# Arduino_DDS_Shield_Rev_6.net
KiCad netlist of a schematic drawn in Altium Designer
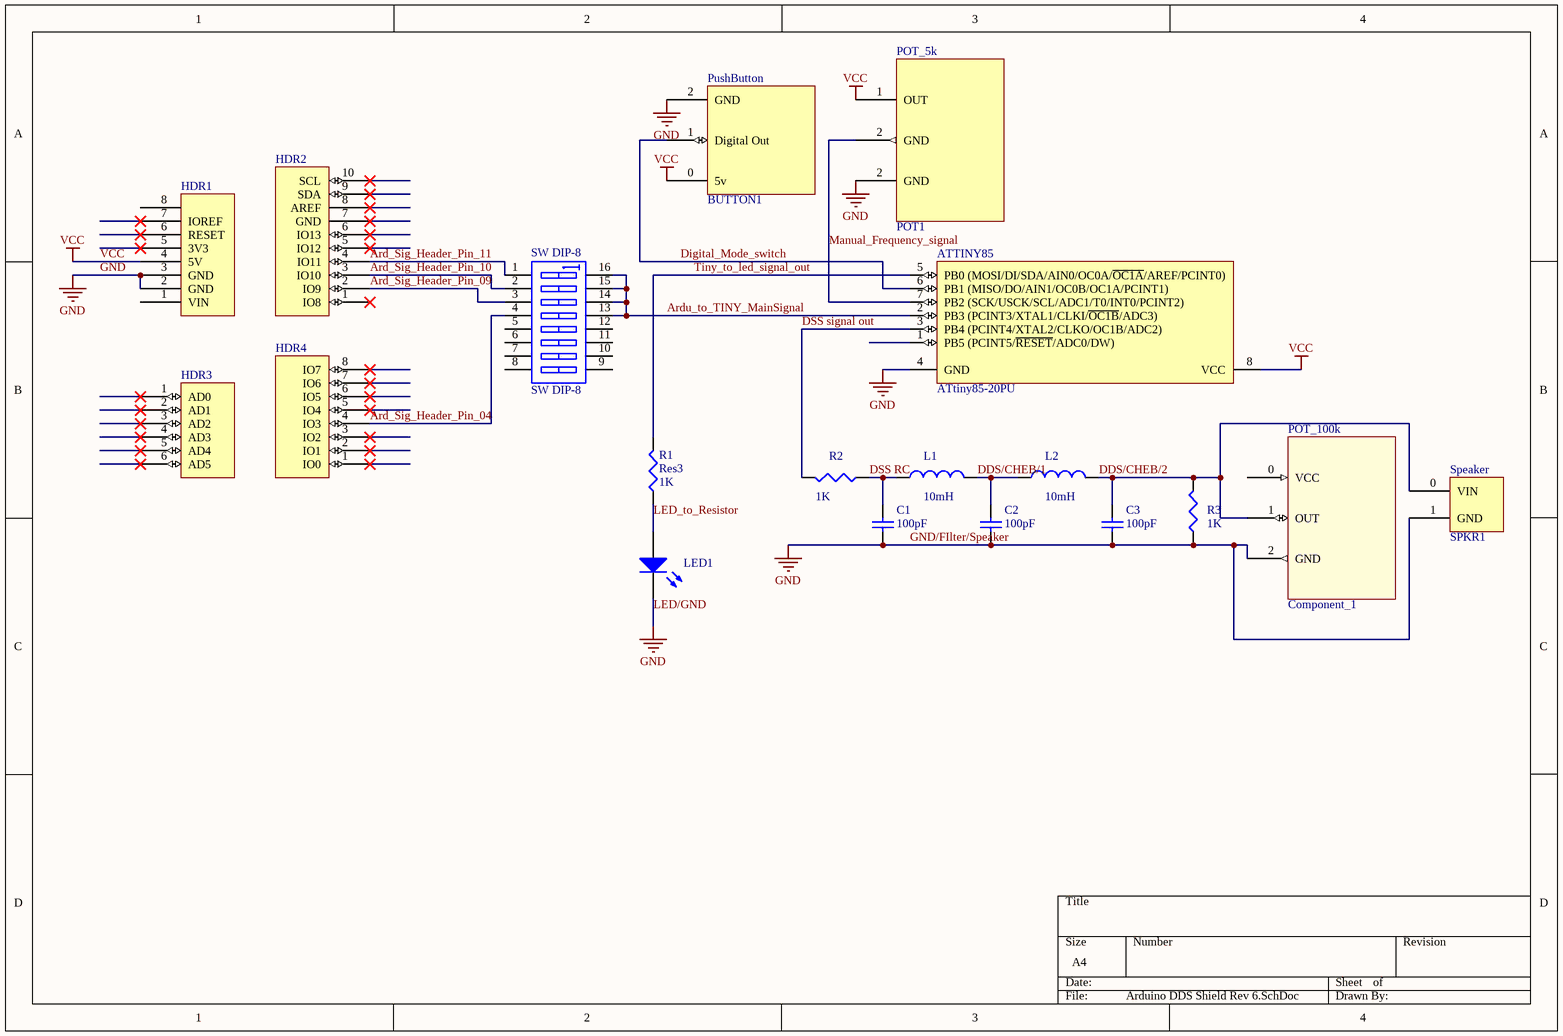
[diagram p0: Arduino DDS Shield Rev 6.SchDoc]

(export (version "E")
  (design (tool "Eeschema 10.0.6"))
  (components
    (comp (ref "ATTINY85")
      (value "ATtiny85-20PU")
      (footprint "8P3")
      (fields (field (name "PUBLISHER") "Altium Limited"))
      (libsource (lib "Atmel Microcontroller 8-Bit tinyAVR") (part "ATtiny85-20PU"))
    )
    (comp (ref "C1")
      (value "100pF")
      (footprint "1608[0603]")
      (description "Capacitor (Semiconductor SIM Model)")
      (fields (field (name "Comment") "Cap Semi") (field (name "PUBLISHER") "Altium Limited"))
      (libsource (lib "Miscellaneous Devices") (part "Cap Semi"))
    )
    (comp (ref "C2")
      (value "100pF")
      (footprint "1608[0603]")
      (description "Capacitor (Semiconductor SIM Model)")
      (fields (field (name "Comment") "Cap Semi") (field (name "PUBLISHER") "Altium Limited"))
      (libsource (lib "Miscellaneous Devices") (part "Cap Semi"))
    )
    (comp (ref "C3")
      (value "100pF")
      (footprint "1608[0603]")
      (description "Capacitor (Semiconductor SIM Model)")
      (fields (field (name "Comment") "Cap Semi") (field (name "PUBLISHER") "Altium Limited"))
      (libsource (lib "Miscellaneous Devices") (part "Cap Semi"))
    )
    (comp (ref "HDR1")
      (value "POWER_UNO")
      (footprint "Header 8x1 8.5mm")
      (libsource (lib "Header") (part "POWER_UNO"))
    )
    (comp (ref "HDR2")
      (value "IOH")
      (footprint "Header:Header 10x1 8.5mm")
      (libsource (lib "Header") (part "IOH"))
    )
    (comp (ref "HDR3")
      (value "AD")
      (footprint "Header:Header 6x1 8.5mm")
      (libsource (lib "Header") (part "AD"))
    )
    (comp (ref "HDR4") (value "IOL") (footprint "Header 8x1 8.5mm") (libsource (lib "Header") (part "IOL")))
    (comp (ref "L1")
      (value "10mH")
      (footprint "AXIAL-0.5")
      (description "Inductor")
      (fields (field (name "PUBLISHER") "Altium Limited"))
      (libsource (lib "Miscellaneous Devices") (part "Inductor"))
    )
    (comp (ref "L2")
      (value "10mH")
      (footprint "AXIAL-0.5")
      (description "Inductor")
      (fields (field (name "PUBLISHER") "Altium Limited"))
      (libsource (lib "Miscellaneous Devices") (part "Inductor"))
    )
    (comp (ref "LED1")
      (value "LED1")
      (footprint "LED-1")
      (description "Typical RED GaAs LED")
      (fields (field (name "PUBLISHER") "Altium Limited"))
      (libsource (lib "Miscellaneous Devices") (part "LED1"))
    )
    (comp (ref "POT_5k")
      (value "POT1")
      (footprint "Pot5k")
      (description "5k RES")
      (libsource (lib "PotLib_Rev_5") (part "Component_1"))
    )
    (comp (ref "POT_100k")
      (value "Component_1")
      (footprint "pot100k")
      (description "5k RES")
      (libsource (lib "PotLib_v_2") (part "Component_1"))
    )
    (comp (ref "PushButton")
      (value "BUTTON1")
      (footprint "PushButtonFrame")
      (libsource (lib "Pushbutton_V_5") (part "PushButton"))
    )
    (comp (ref "R1")
      (value "Res3")
      (footprint "J1-0603")
      (description "Resistor")
      (fields (field (name "ALTIUM_VALUE") "1K") (field (name "PUBLISHER") "Altium Limited"))
      (libsource (lib "Miscellaneous Devices") (part "Res3"))
    )
    (comp (ref "R2")
      (value "1K")
      (footprint "J1-0603")
      (description "Resistor")
      (fields (field (name "Comment") "Res3") (field (name "PUBLISHER") "Altium Limited"))
      (libsource (lib "Miscellaneous Devices") (part "Res3"))
    )
    (comp (ref "R3")
      (value "1K")
      (footprint "J1-0603")
      (description "Resistor")
      (fields (field (name "Comment") "Res3") (field (name "PUBLISHER") "Altium Limited"))
      (libsource (lib "Miscellaneous Devices") (part "Res3"))
    )
    (comp (ref "Speaker")
      (value "SPKR1")
      (footprint "PCBComponent_1")
      (libsource (lib "Schlib1_rev_01") (part "Component_1"))
    )
    (comp (ref "SW DIP-8")
      (value "SW DIP-8")
      (footprint "DIP8posSolder")
      (description "DIP Switch, 8 Position, SPST")
      (fields (field (name "PUBLISHER") "Altium Limited"))
      (libsource (lib "Miscellaneous Devices") (part "SW DIP-8"))
    )
  )
  (nets
    (net (code "2") (name "/Ard_Sig_Header_Pin_04") (class "Default")
      (node (ref "HDR4") (pin "4") (pinfunction "IO3_4") (pintype "bidirectional"))
      (node (ref "SW DIP-8") (pin "4") (pinfunction "A4_4") (pintype "passive"))
    )
    (net (code "3") (name "/Ard_Sig_Header_Pin_09") (class "Default")
      (node (ref "HDR2") (pin "2") (pinfunction "IO9_2") (pintype "bidirectional"))
      (node (ref "SW DIP-8") (pin "3") (pinfunction "A3_3") (pintype "passive"))
    )
    (net (code "4") (name "/Ard_Sig_Header_Pin_10") (class "Default")
      (node (ref "HDR2") (pin "3") (pinfunction "IO10_3") (pintype "bidirectional"))
      (node (ref "SW DIP-8") (pin "2") (pinfunction "A2_2") (pintype "passive"))
    )
    (net (code "5") (name "/Ard_Sig_Header_Pin_11") (class "Default")
      (node (ref "HDR2") (pin "4") (pinfunction "IO11_4") (pintype "bidirectional"))
      (node (ref "SW DIP-8") (pin "1") (pinfunction "A1_1") (pintype "passive"))
    )
    (net (code "6") (name "/Ardu_to_TINY_MainSignal") (class "Default")
      (node (ref "ATTINY85") (pin "2") (pinfunction "PB3_(PCINT3/XTAL1/CLKI/~{OC1B}/ADC3)_2") (pintype "bidirectional"))
      (node (ref "SW DIP-8") (pin "13") (pinfunction "B4_13") (pintype "passive"))
      (node (ref "SW DIP-8") (pin "14") (pinfunction "B3_14") (pintype "passive"))
      (node (ref "SW DIP-8") (pin "15") (pinfunction "B2_15") (pintype "passive"))
      (node (ref "SW DIP-8") (pin "16") (pinfunction "B1_16") (pintype "passive"))
    )
    (net (code "7") (name "/DDS{slash}CHEB{slash}1") (class "Default")
      (node (ref "C2") (pin "2") (pinfunction "2_2") (pintype "passive"))
      (node (ref "L1") (pin "2") (pinfunction "2_2") (pintype "passive"))
      (node (ref "L2") (pin "1") (pinfunction "1_1") (pintype "passive"))
    )
    (net (code "8") (name "/DDS{slash}CHEB{slash}2") (class "Default")
      (node (ref "C3") (pin "2") (pinfunction "2_2") (pintype "passive"))
      (node (ref "L2") (pin "2") (pinfunction "2_2") (pintype "passive"))
      (node (ref "POT_100k") (pin "1") (pinfunction "OUT_1") (pintype "bidirectional"))
      (node (ref "R3") (pin "2") (pinfunction "2_2") (pintype "passive"))
      (node (ref "Speaker") (pin "0") (pinfunction "VIN_0") (pintype "power_in"))
    )
    (net (code "9") (name "/DSS RC") (class "Default")
      (node (ref "C1") (pin "2") (pinfunction "2_2") (pintype "passive"))
      (node (ref "L1") (pin "1") (pinfunction "1_1") (pintype "passive"))
      (node (ref "R2") (pin "1") (pinfunction "1_1") (pintype "passive"))
    )
    (net (code "10") (name "/DSS signal out") (class "Default")
      (node (ref "ATTINY85") (pin "3") (pinfunction "PB4_(PCINT4/XTAL2/CLKO/OC1B/ADC2)_3") (pintype "bidirectional"))
      (node (ref "R2") (pin "2") (pinfunction "2_2") (pintype "passive"))
    )
    (net (code "11") (name "/Digital_Mode_switch") (class "Default")
      (node (ref "ATTINY85") (pin "6") (pinfunction "PB1_(MISO/DO/AIN1/OC0B/OC1A/PCINT1)_6") (pintype "bidirectional"))
      (node (ref "PushButton") (pin "1") (pinfunction "Digital_Out_1") (pintype "bidirectional"))
    )
    (net (code "12") (name "/LED_to_Resistor") (class "Default")
      (node (ref "LED1") (pin "1") (pinfunction "A_1") (pintype "passive"))
      (node (ref "R1") (pin "1") (pinfunction "1_1") (pintype "passive"))
    )
    (net (code "13") (name "/Manual_Frequency_signal") (class "Default")
      (node (ref "ATTINY85") (pin "7") (pinfunction "PB2_(SCK/USCK/SCL/ADC1/T0/INT0/PCINT2)_7") (pintype "bidirectional"))
      (node (ref "POT_5k") (pin "2") (pinfunction "GND_2") (pintype "output"))
    )
    (net (code "14") (name "/Tiny_to_led_signal_out") (class "Default")
      (node (ref "ATTINY85") (pin "5") (pinfunction "PB0_(MOSI/DI/SDA/AIN0/OC0A/~{OC1A}/AREF/PCINT0)_5") (pintype "bidirectional"))
      (node (ref "R1") (pin "2") (pinfunction "2_2") (pintype "passive"))
    )
    (net (code "15") (name "GND") (class "Default")
      (node (ref "ATTINY85") (pin "4") (pinfunction "GND_4") (pintype "power_in"))
      (node (ref "C1") (pin "1") (pinfunction "1_1") (pintype "passive"))
      (node (ref "C2") (pin "1") (pinfunction "1_1") (pintype "passive"))
      (node (ref "C3") (pin "1") (pinfunction "1_1") (pintype "passive"))
      (node (ref "HDR1") (pin "2") (pinfunction "GND_2") (pintype "power_in"))
      (node (ref "HDR1") (pin "3") (pinfunction "GND_3") (pintype "power_in"))
      (node (ref "LED1") (pin "2") (pinfunction "K_2") (pintype "passive"))
      (node (ref "POT_100k") (pin "2") (pinfunction "GND_2") (pintype "output"))
      (node (ref "POT_5k") (pin "2") (pinfunction "GND_2") (pintype "power_in"))
      (node (ref "PushButton") (pin "2") (pinfunction "GND_2") (pintype "power_in"))
      (node (ref "R3") (pin "1") (pinfunction "1_1") (pintype "passive"))
      (node (ref "Speaker") (pin "1") (pinfunction "GND_1") (pintype "power_in"))
    )
    (net (code "16") (name "VCC") (class "Default")
      (node (ref "ATTINY85") (pin "8") (pinfunction "VCC_8") (pintype "power_in"))
      (node (ref "HDR1") (pin "4") (pinfunction "5V_4") (pintype "power_in"))
      (node (ref "POT_5k") (pin "1") (pinfunction "OUT_1") (pintype "power_in"))
      (node (ref "PushButton") (pin "0") (pinfunction "5v_0") (pintype "power_in"))
    )
    (net (code "17") (name "unconnected-(ATTINY85-PB5_(PCINT5{slash}~{RESET}{slash}ADC0{slash}DW)-Pad1)") (class "Default")
      (node (ref "ATTINY85") (pin "1") (pinfunction "PB5_(PCINT5/~{RESET}/ADC0/DW)_1") (pintype "bidirectional"))
    )
    (net (code "18") (name "unconnected-(HDR1-3V3-Pad5)") (class "Default")
      (node (ref "HDR1") (pin "5") (pinfunction "3V3_5") (pintype "power_in+no_connect"))
    )
    (net (code "19") (name "unconnected-(HDR1-IOREF-Pad7)") (class "Default")
      (node (ref "HDR1") (pin "7") (pinfunction "IOREF_7") (pintype "power_in+no_connect"))
    )
    (net (code "20") (name "unconnected-(HDR1-Pad8)") (class "Default")
      (node (ref "HDR1") (pin "8") (pintype "passive"))
    )
    (net (code "21") (name "unconnected-(HDR1-RESET-Pad6)") (class "Default")
      (node (ref "HDR1") (pin "6") (pinfunction "RESET_6") (pintype "passive+no_connect"))
    )
    (net (code "22") (name "unconnected-(HDR1-VIN-Pad1)") (class "Default")
      (node (ref "HDR1") (pin "1") (pinfunction "VIN_1") (pintype "power_in"))
    )
    (net (code "23") (name "unconnected-(HDR2-AREF-Pad8)") (class "Default")
      (node (ref "HDR2") (pin "8") (pinfunction "AREF_8") (pintype "passive+no_connect"))
    )
    (net (code "24") (name "unconnected-(HDR2-GND-Pad7)") (class "Default")
      (node (ref "HDR2") (pin "7") (pinfunction "GND_7") (pintype "power_in+no_connect"))
    )
    (net (code "25") (name "unconnected-(HDR2-IO8-Pad1)") (class "Default")
      (node (ref "HDR2") (pin "1") (pinfunction "IO8_1") (pintype "bidirectional+no_connect"))
    )
    (net (code "26") (name "unconnected-(HDR2-IO12-Pad5)") (class "Default")
      (node (ref "HDR2") (pin "5") (pinfunction "IO12_5") (pintype "bidirectional+no_connect"))
    )
    (net (code "27") (name "unconnected-(HDR2-IO13-Pad6)") (class "Default")
      (node (ref "HDR2") (pin "6") (pinfunction "IO13_6") (pintype "bidirectional+no_connect"))
    )
    (net (code "28") (name "unconnected-(HDR2-SCL-Pad10)") (class "Default")
      (node (ref "HDR2") (pin "10") (pinfunction "SCL_10") (pintype "bidirectional+no_connect"))
    )
    (net (code "29") (name "unconnected-(HDR2-SDA-Pad9)") (class "Default")
      (node (ref "HDR2") (pin "9") (pinfunction "SDA_9") (pintype "bidirectional+no_connect"))
    )
    (net (code "30") (name "unconnected-(HDR3-AD0-Pad1)") (class "Default")
      (node (ref "HDR3") (pin "1") (pinfunction "AD0_1") (pintype "bidirectional+no_connect"))
    )
    (net (code "31") (name "unconnected-(HDR3-AD1-Pad2)") (class "Default")
      (node (ref "HDR3") (pin "2") (pinfunction "AD1_2") (pintype "bidirectional+no_connect"))
    )
    (net (code "32") (name "unconnected-(HDR3-AD2-Pad3)") (class "Default")
      (node (ref "HDR3") (pin "3") (pinfunction "AD2_3") (pintype "bidirectional+no_connect"))
    )
    (net (code "33") (name "unconnected-(HDR3-AD3-Pad4)") (class "Default")
      (node (ref "HDR3") (pin "4") (pinfunction "AD3_4") (pintype "bidirectional+no_connect"))
    )
    (net (code "34") (name "unconnected-(HDR3-AD4-Pad5)") (class "Default")
      (node (ref "HDR3") (pin "5") (pinfunction "AD4_5") (pintype "bidirectional+no_connect"))
    )
    (net (code "35") (name "unconnected-(HDR3-AD5-Pad6)") (class "Default")
      (node (ref "HDR3") (pin "6") (pinfunction "AD5_6") (pintype "bidirectional+no_connect"))
    )
    (net (code "36") (name "unconnected-(HDR4-IO0-Pad1)") (class "Default")
      (node (ref "HDR4") (pin "1") (pinfunction "IO0_1") (pintype "bidirectional+no_connect"))
    )
    (net (code "37") (name "unconnected-(HDR4-IO1-Pad2)") (class "Default")
      (node (ref "HDR4") (pin "2") (pinfunction "IO1_2") (pintype "bidirectional+no_connect"))
    )
    (net (code "38") (name "unconnected-(HDR4-IO2-Pad3)") (class "Default")
      (node (ref "HDR4") (pin "3") (pinfunction "IO2_3") (pintype "bidirectional+no_connect"))
    )
    (net (code "39") (name "unconnected-(HDR4-IO4-Pad5)") (class "Default")
      (node (ref "HDR4") (pin "5") (pinfunction "IO4_5") (pintype "bidirectional+no_connect"))
    )
    (net (code "40") (name "unconnected-(HDR4-IO5-Pad6)") (class "Default")
      (node (ref "HDR4") (pin "6") (pinfunction "IO5_6") (pintype "bidirectional+no_connect"))
    )
    (net (code "41") (name "unconnected-(HDR4-IO6-Pad7)") (class "Default")
      (node (ref "HDR4") (pin "7") (pinfunction "IO6_7") (pintype "bidirectional+no_connect"))
    )
    (net (code "42") (name "unconnected-(HDR4-IO7-Pad8)") (class "Default")
      (node (ref "HDR4") (pin "8") (pinfunction "IO7_8") (pintype "bidirectional+no_connect"))
    )
    (net (code "43") (name "unconnected-(POT_100k-VCC-Pad0)") (class "Default")
      (node (ref "POT_100k") (pin "0") (pinfunction "VCC_0") (pintype "input"))
    )
    (net (code "44") (name "unconnected-(SW DIP-8-A5-Pad5)") (class "Default")
      (node (ref "SW DIP-8") (pin "5") (pinfunction "A5_5") (pintype "passive"))
    )
    (net (code "45") (name "unconnected-(SW DIP-8-A6-Pad6)") (class "Default")
      (node (ref "SW DIP-8") (pin "6") (pinfunction "A6_6") (pintype "passive"))
    )
    (net (code "46") (name "unconnected-(SW DIP-8-A7-Pad7)") (class "Default")
      (node (ref "SW DIP-8") (pin "7") (pinfunction "A7_7") (pintype "passive"))
    )
    (net (code "47") (name "unconnected-(SW DIP-8-A8-Pad8)") (class "Default")
      (node (ref "SW DIP-8") (pin "8") (pinfunction "A8_8") (pintype "passive"))
    )
    (net (code "48") (name "unconnected-(SW DIP-8-B5-Pad12)") (class "Default")
      (node (ref "SW DIP-8") (pin "12") (pinfunction "B5_12") (pintype "passive"))
    )
    (net (code "49") (name "unconnected-(SW DIP-8-B6-Pad11)") (class "Default")
      (node (ref "SW DIP-8") (pin "11") (pinfunction "B6_11") (pintype "passive"))
    )
    (net (code "50") (name "unconnected-(SW DIP-8-B7-Pad10)") (class "Default")
      (node (ref "SW DIP-8") (pin "10") (pinfunction "B7_10") (pintype "passive"))
    )
    (net (code "51") (name "unconnected-(SW DIP-8-B8-Pad9)") (class "Default")
      (node (ref "SW DIP-8") (pin "9") (pinfunction "B8_9") (pintype "passive"))
    )
  )
)
